# OpAmp.net
KiCad netlist of a schematic drawn in EAGLE
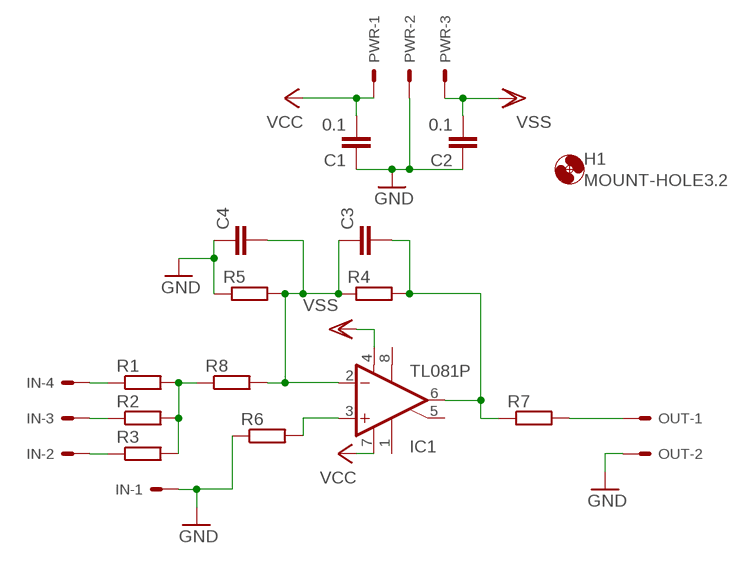
[diagram p0: schematic, sheet 1]

(export (version "E")
  (design (tool "Eeschema 10.0.6"))
  (components
    (comp (ref "C1")
      (value "0.1")
      (footprint "eagle-import:C050-030X075")
      (libsource (lib "eagle-import") (part "C-EU050-030X075"))
    )
    (comp (ref "C2")
      (value "0.1")
      (footprint "eagle-import:C050-030X075")
      (libsource (lib "eagle-import") (part "C-EU050-030X075"))
    )
    (comp (ref "C3")
      (value "C-EU050-030X075")
      (footprint "eagle-import:C050-030X075")
      (libsource (lib "eagle-import") (part "C-EU050-030X075"))
    )
    (comp (ref "C4")
      (value "C-EU050-030X075")
      (footprint "eagle-import:C050-030X075")
      (libsource (lib "eagle-import") (part "C-EU050-030X075"))
    )
    (comp (ref "H1")
      (value "MOUNT-HOLE3.2")
      (footprint "eagle-import:3,2")
      (libsource (lib "eagle-import") (part "MOUNT-HOLE3.2"))
    )
    (comp (ref "IC1")
      (value "TL081P")
      (footprint "eagle-import:DIL08")
      (libsource (lib "eagle-import") (part "TL081P"))
    )
    (comp (ref "IN")
      (value "22-27-2041-04")
      (footprint "eagle-import:6410-04")
      (libsource (lib "eagle-import") (part "22-?-0427-2041"))
    )
    (comp (ref "OUT")
      (value "22-27-2021-02")
      (footprint "eagle-import:6410-02")
      (libsource (lib "eagle-import") (part "22-?-0227-2021"))
    )
    (comp (ref "PWR")
      (value "22-27-2031-03")
      (footprint "eagle-import:6410-03")
      (libsource (lib "eagle-import") (part "22-?-0327-2031"))
    )
    (comp (ref "R1")
      (value "R-EU_0204/7")
      (footprint "eagle-import:0204_7")
      (libsource (lib "eagle-import") (part "R-EU_0204/7"))
    )
    (comp (ref "R2")
      (value "R-EU_0204/7")
      (footprint "eagle-import:0204_7")
      (libsource (lib "eagle-import") (part "R-EU_0204/7"))
    )
    (comp (ref "R3")
      (value "R-EU_0204/7")
      (footprint "eagle-import:0204_7")
      (libsource (lib "eagle-import") (part "R-EU_0204/7"))
    )
    (comp (ref "R4")
      (value "R-EU_0204/7")
      (footprint "eagle-import:0204_7")
      (libsource (lib "eagle-import") (part "R-EU_0204/7"))
    )
    (comp (ref "R5")
      (value "R-EU_0204/7")
      (footprint "eagle-import:0204_7")
      (libsource (lib "eagle-import") (part "R-EU_0204/7"))
    )
    (comp (ref "R6")
      (value "R-EU_0204/7")
      (footprint "eagle-import:0204_7")
      (libsource (lib "eagle-import") (part "R-EU_0204/7"))
    )
    (comp (ref "R7")
      (value "R-EU_0204/7")
      (footprint "eagle-import:0204_7")
      (libsource (lib "eagle-import") (part "R-EU_0204/7"))
    )
    (comp (ref "R8")
      (value "R-EU_0204/7")
      (footprint "eagle-import:0204_7")
      (libsource (lib "eagle-import") (part "R-EU_0204/7"))
    )
  )
  (nets
    (net (code "1") (name "GND") (class "Default")
      (node (ref "C1") (pin "1") (pinfunction "1_1") (pintype "passive"))
      (node (ref "C2") (pin "1") (pinfunction "1_1") (pintype "passive"))
      (node (ref "C4") (pin "1") (pinfunction "1_1") (pintype "passive"))
      (node (ref "IN") (pin "1") (pinfunction "S_1") (pintype "passive"))
      (node (ref "OUT") (pin "2") (pinfunction "S_2") (pintype "passive"))
      (node (ref "PWR") (pin "2") (pinfunction "S_2") (pintype "passive"))
      (node (ref "R5") (pin "1") (pinfunction "1_1") (pintype "passive"))
      (node (ref "R6") (pin "1") (pinfunction "1_1") (pintype "passive"))
    )
    (net (code "2") (name "Net-(IC1-+IN)") (class "Default")
      (node (ref "IC1") (pin "3") (pinfunction "+IN_3") (pintype "input"))
      (node (ref "R6") (pin "2") (pinfunction "2_2") (pintype "passive"))
    )
    (net (code "3") (name "Net-(IC1--IN)") (class "Default")
      (node (ref "C3") (pin "1") (pinfunction "1_1") (pintype "passive"))
      (node (ref "C4") (pin "2") (pinfunction "2_2") (pintype "passive"))
      (node (ref "IC1") (pin "2") (pinfunction "-IN_2") (pintype "input"))
      (node (ref "R4") (pin "1") (pinfunction "1_1") (pintype "passive"))
      (node (ref "R5") (pin "2") (pinfunction "2_2") (pintype "passive"))
      (node (ref "R8") (pin "2") (pinfunction "2_2") (pintype "passive"))
    )
    (net (code "4") (name "Net-(IC1-OUT)") (class "Default")
      (node (ref "C3") (pin "2") (pinfunction "2_2") (pintype "passive"))
      (node (ref "IC1") (pin "6") (pinfunction "OUT_6") (pintype "output"))
      (node (ref "R4") (pin "2") (pinfunction "2_2") (pintype "passive"))
      (node (ref "R7") (pin "1") (pinfunction "1_1") (pintype "passive"))
    )
    (net (code "5") (name "Net-(INB-S)") (class "Default")
      (node (ref "IN") (pin "2") (pinfunction "S_2") (pintype "passive"))
      (node (ref "R3") (pin "1") (pinfunction "1_1") (pintype "passive"))
    )
    (net (code "6") (name "Net-(INC-S)") (class "Default")
      (node (ref "IN") (pin "3") (pinfunction "S_3") (pintype "passive"))
      (node (ref "R2") (pin "1") (pinfunction "1_1") (pintype "passive"))
    )
    (net (code "7") (name "Net-(IND-S)") (class "Default")
      (node (ref "IN") (pin "4") (pinfunction "S_4") (pintype "passive"))
      (node (ref "R1") (pin "1") (pinfunction "1_1") (pintype "passive"))
    )
    (net (code "8") (name "Net-(OUTA-S)") (class "Default")
      (node (ref "OUT") (pin "1") (pinfunction "S_1") (pintype "passive"))
      (node (ref "R7") (pin "2") (pinfunction "2_2") (pintype "passive"))
    )
    (net (code "9") (name "Net-(R1-Pad2)") (class "Default")
      (node (ref "R1") (pin "2") (pinfunction "2_2") (pintype "passive"))
      (node (ref "R2") (pin "2") (pinfunction "2_2") (pintype "passive"))
      (node (ref "R3") (pin "2") (pinfunction "2_2") (pintype "passive"))
      (node (ref "R8") (pin "1") (pinfunction "1_1") (pintype "passive"))
    )
    (net (code "10") (name "VCC") (class "Default")
      (node (ref "C1") (pin "2") (pinfunction "2_2") (pintype "passive"))
      (node (ref "IC1") (pin "7") (pinfunction "V+_7") (pintype "power_in"))
      (node (ref "PWR") (pin "1") (pinfunction "S_1") (pintype "passive"))
    )
    (net (code "11") (name "VSS") (class "Default")
      (node (ref "C2") (pin "2") (pinfunction "2_2") (pintype "passive"))
      (node (ref "IC1") (pin "4") (pinfunction "V-_4") (pintype "power_in"))
      (node (ref "PWR") (pin "3") (pinfunction "S_3") (pintype "passive"))
    )
    (net (code "12") (name "unconnected-(IC1-ON1-Pad1)") (class "Default")
      (node (ref "IC1") (pin "1") (pinfunction "ON1_1") (pintype "passive"))
    )
    (net (code "13") (name "unconnected-(IC1-ON2-Pad5)") (class "Default")
      (node (ref "IC1") (pin "5") (pinfunction "ON2_5") (pintype "passive"))
    )
    (net (code "14") (name "unconnected-(IC1-OPT-Pad8)") (class "Default")
      (node (ref "IC1") (pin "8") (pinfunction "OPT_8") (pintype "passive"))
    )
  )
)
